# PICkit3_Extender.net
KiCad netlist of a schematic drawn in EAGLE
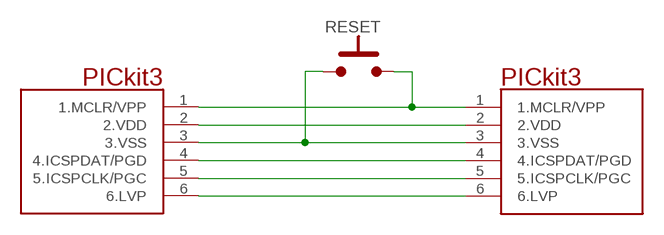
[diagram p0: schematic, sheet 1]

(export (version "E")
  (design (tool "Eeschema 10.0.6"))
  (components
    (comp (ref "RESET")
      (value "PUSHBUTTON")
      (footprint "eagle-import:TL1105")
      (libsource (lib "eagle-import") (part "PUSHBUTTON"))
    )
    (comp (ref "U$1")
      (value "PICKIT3")
      (footprint "eagle-import:PINS_6_PICKIT3")
      (libsource (lib "eagle-import") (part "PICKIT3"))
    )
    (comp (ref "U$3")
      (value "PICKIT3PLAIN")
      (footprint "eagle-import:PINS_6")
      (libsource (lib "eagle-import") (part "PICKIT3PLAIN"))
    )
  )
  (nets
    (net (code "1") (name "Net-(U$1-1.MCLR{slash}VPP)") (class "Default")
      (node (ref "RESET") (pin "2") (pinfunction "2_2") (pintype "bidirectional"))
      (node (ref "RESET") (pin "4") (pinfunction "2_4") (pintype "bidirectional"))
      (node (ref "U$1") (pin "1") (pinfunction "1.MCLR/VPP_1") (pintype "bidirectional"))
      (node (ref "U$3") (pin "1") (pinfunction "1.MCLR/VPP_1") (pintype "bidirectional"))
    )
    (net (code "2") (name "Net-(U$1-2.VDD)") (class "Default")
      (node (ref "U$1") (pin "2") (pinfunction "2.VDD_2") (pintype "bidirectional"))
      (node (ref "U$3") (pin "2") (pinfunction "2.VDD_2") (pintype "bidirectional"))
    )
    (net (code "3") (name "Net-(U$1-3.VSS)") (class "Default")
      (node (ref "RESET") (pin "1") (pinfunction "1_1") (pintype "bidirectional"))
      (node (ref "RESET") (pin "3") (pinfunction "1_3") (pintype "bidirectional"))
      (node (ref "U$1") (pin "3") (pinfunction "3.VSS_3") (pintype "bidirectional"))
      (node (ref "U$3") (pin "3") (pinfunction "3.VSS_3") (pintype "bidirectional"))
    )
    (net (code "4") (name "Net-(U$1-4.ICSPDAT{slash}PGD)") (class "Default")
      (node (ref "U$1") (pin "4") (pinfunction "4.ICSPDAT/PGD_4") (pintype "bidirectional"))
      (node (ref "U$3") (pin "4") (pinfunction "4.ICSPDAT/PGD_4") (pintype "bidirectional"))
    )
    (net (code "5") (name "Net-(U$1-5.ICSPCLK{slash}PGC)") (class "Default")
      (node (ref "U$1") (pin "5") (pinfunction "5.ICSPCLK/PGC_5") (pintype "bidirectional"))
      (node (ref "U$3") (pin "5") (pinfunction "5.ICSPCLK/PGC_5") (pintype "bidirectional"))
    )
    (net (code "6") (name "Net-(U$1-6.LVP)") (class "Default")
      (node (ref "U$1") (pin "6") (pinfunction "6.LVP_6") (pintype "bidirectional"))
      (node (ref "U$3") (pin "6") (pinfunction "6.LVP_6") (pintype "bidirectional"))
    )
  )
)
